# pir.net
KiCad netlist of a schematic drawn in Altium Designer
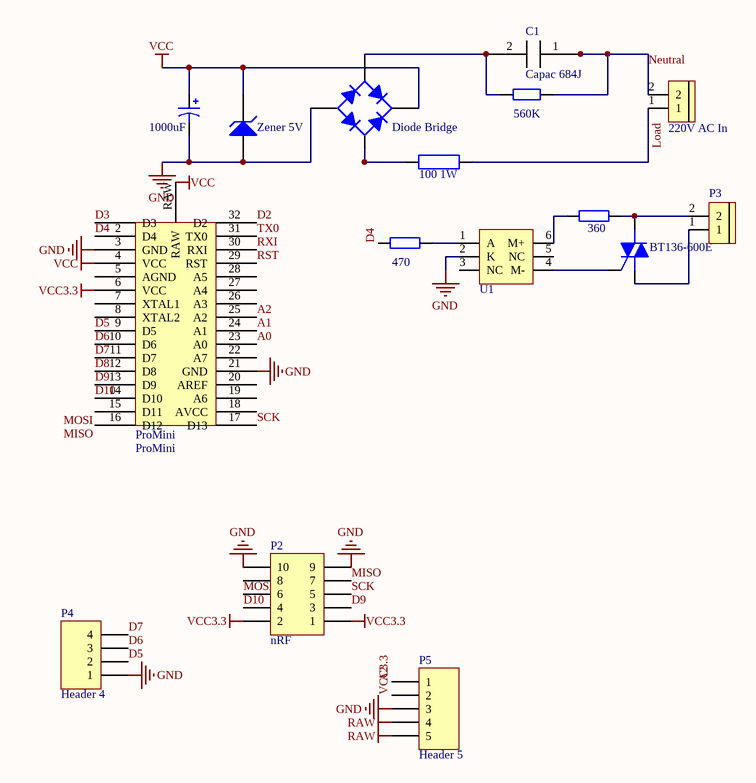
[diagram p0: pir.SchDoc]

(export (version "E")
  (design (tool "Eeschema 10.0.6"))
  (components
    (comp (ref "C1")
      (value "Capac 684J")
      (footprint "Tu keo 684J 400V")
      (libsource (lib "ArduinoLib") (part "Tu keo 684J 400V"))
    )
    (comp (ref "C3")
      (value "1000uF")
      (footprint "C10mm")
      (description "Polarized Capacitor (Axial)")
      (fields (field (name "PUBLISHER") "Altium Limited"))
      (libsource (lib "NBBLib 14-03-2012") (part "Cap Pol 8mm"))
    )
    (comp (ref "D1")
      (value "Diode Bridge")
      (footprint "D-38")
      (description "Full Wave Diode Bridge")
      (fields (field (name "PUBLISHER") "Altium Limited"))
      (libsource (lib "Miscellaneous Devices") (part "Bridge1"))
    )
    (comp (ref "D3")
      (value "Zener 5V")
      (footprint "DIODE/NOM/0.5A")
      (description "Zener Diode")
      (fields (field (name "VOLTAGE") "5") (field (name "PUBLISHER") "Altium Limited"))
      (libsource (lib "NBBLib 14-03-2012") (part "Diode Zener"))
    )
    (comp (ref "P1")
      (value "220V AC In")
      (footprint "BIG_Header 2")
      (libsource (lib "NBBLib 14-03-2012") (part "BIG_Header 2"))
    )
    (comp (ref "P2")
      (value "nRF")
      (footprint "HDR2X5")
      (description "Header, 5-Pin, Dual row")
      (fields (field (name "PUBLISHER") "Altium Limited"))
      (libsource (lib "Miscellaneous Connectors") (part "Header 5X2"))
    )
    (comp (ref "P3")
      (value "BIG_Header 2")
      (footprint "BIG_Header 2")
      (libsource (lib "NBBLib 14-03-2012") (part "BIG_Header 2"))
    )
    (comp (ref "P4")
      (value "Header 4")
      (footprint "HDR1X4")
      (description "Header, 4-Pin")
      (fields (field (name "PUBLISHER") "Altium Limited"))
      (libsource (lib "Miscellaneous Connectors") (part "Header 4"))
    )
    (comp (ref "P5")
      (value "Header 5")
      (footprint "HDR1X5")
      (description "Header, 5-Pin")
      (fields (field (name "PUBLISHER") "Altium Limited"))
      (libsource (lib "NBBLib 14-03-2012") (part "Header 5"))
    )
    (comp (ref "ProMini")
      (value "ProMini")
      (footprint "Arduino Pro Mini")
      (libsource (lib "ArduinoLib") (part "Pro Mini"))
    )
    (comp (ref "Q1")
      (value "BT136-600E")
      (footprint "BTA6-600")
      (description "Silicon Bidirectional Triode Thyristor")
      (fields (field (name "PUBLISHER") "Altium Limited"))
      (libsource (lib "NBBLib 14-03-2012") (part "BTA12-600"))
    )
    (comp (ref "R1")
      (value "100 1W")
      (footprint "DIEN TRO 1W (tube)")
      (description "1W Res Power")
      (fields (field (name "VOLTAGE") "400") (field (name "CREATOR") "Nguyen Ba Bien"))
      (libsource (lib "NBBLib 14-03-2012") (part "Res 1W"))
    )
    (comp (ref "R3")
      (value "560K")
      (footprint "AXIAL-0.4")
      (description "Resistor")
      (fields (field (name "PUBLISHER") "Altium Limited"))
      (libsource (lib "Miscellaneous Devices") (part "Res2"))
    )
    (comp (ref "R4")
      (value "470")
      (footprint "R1/4W")
      (description "Resistor")
      (libsource (lib "t.thien") (part "R1/4W"))
    )
    (comp (ref "R5")
      (value "360")
      (footprint "R1/4W")
      (description "Resistor")
      (libsource (lib "t.thien") (part "R1/4W"))
    )
    (comp (ref "U1")
      (value "MOC3021M")
      (footprint "MOC30XX")
      (libsource (lib "NBBLib 14-03-2012") (part "MOC3021M"))
    )
  )
  (nets
    (net (code "1") (name "/A0") (class "Default")
      (node (ref "ProMini") (pin "23") (pinfunction "A0_23") (pintype "passive"))
    )
    (net (code "2") (name "/A1") (class "Default")
      (node (ref "ProMini") (pin "24") (pinfunction "A1_24") (pintype "passive"))
    )
    (net (code "3") (name "/A2") (class "Default")
      (node (ref "P5") (pin "1") (pinfunction "1_1") (pintype "passive"))
      (node (ref "ProMini") (pin "25") (pinfunction "A2_25") (pintype "passive"))
    )
    (net (code "4") (name "/D2") (class "Default")
      (node (ref "ProMini") (pin "32") (pinfunction "D2_32") (pintype "passive"))
    )
    (net (code "5") (name "/D3") (class "Default")
      (node (ref "ProMini") (pin "1") (pinfunction "D3_1") (pintype "passive"))
    )
    (net (code "6") (name "/D4") (class "Default")
      (node (ref "ProMini") (pin "2") (pinfunction "D4_2") (pintype "passive"))
      (node (ref "R4") (pin "1") (pinfunction "1_1") (pintype "passive"))
    )
    (net (code "7") (name "/D5") (class "Default")
      (node (ref "P4") (pin "2") (pinfunction "2_2") (pintype "passive"))
      (node (ref "ProMini") (pin "9") (pinfunction "D5_9") (pintype "passive"))
    )
    (net (code "8") (name "/D6") (class "Default")
      (node (ref "P4") (pin "3") (pinfunction "3_3") (pintype "passive"))
      (node (ref "ProMini") (pin "10") (pinfunction "D6_10") (pintype "passive"))
    )
    (net (code "9") (name "/D7") (class "Default")
      (node (ref "P4") (pin "4") (pinfunction "4_4") (pintype "passive"))
      (node (ref "ProMini") (pin "11") (pinfunction "D7_11") (pintype "passive"))
    )
    (net (code "10") (name "/D8") (class "Default")
      (node (ref "ProMini") (pin "12") (pinfunction "D8_12") (pintype "passive"))
    )
    (net (code "11") (name "/D9") (class "Default")
      (node (ref "P2") (pin "3") (pinfunction "3_3") (pintype "passive"))
      (node (ref "ProMini") (pin "13") (pinfunction "D9_13") (pintype "passive"))
    )
    (net (code "12") (name "/D10") (class "Default")
      (node (ref "P2") (pin "4") (pinfunction "4_4") (pintype "passive"))
      (node (ref "ProMini") (pin "14") (pinfunction "D10_14") (pintype "passive"))
    )
    (net (code "13") (name "/Load") (class "Default")
      (node (ref "P1") (pin "1") (pinfunction "1_1") (pintype "passive"))
      (node (ref "R1") (pin "2") (pinfunction "2_2") (pintype "passive"))
    )
    (net (code "14") (name "/MISO") (class "Default")
      (node (ref "P2") (pin "7") (pinfunction "7_7") (pintype "passive"))
      (node (ref "ProMini") (pin "16") (pinfunction "D12_16") (pintype "passive"))
    )
    (net (code "15") (name "/MOSI") (class "Default")
      (node (ref "P2") (pin "6") (pinfunction "6_6") (pintype "passive"))
      (node (ref "ProMini") (pin "15") (pinfunction "D11_15") (pintype "passive"))
    )
    (net (code "16") (name "/Neutral") (class "Default")
      (node (ref "C1") (pin "1") (pinfunction "1_1") (pintype "passive"))
      (node (ref "P1") (pin "2") (pinfunction "2_2") (pintype "passive"))
      (node (ref "R3") (pin "2") (pinfunction "2_2") (pintype "passive"))
    )
    (net (code "17") (name "/RST") (class "Default")
      (node (ref "ProMini") (pin "29") (pinfunction "RST_29") (pintype "passive"))
    )
    (net (code "18") (name "/RXI") (class "Default")
      (node (ref "ProMini") (pin "30") (pinfunction "RXI_30") (pintype "passive"))
    )
    (net (code "19") (name "/SCK") (class "Default")
      (node (ref "P2") (pin "5") (pinfunction "5_5") (pintype "passive"))
      (node (ref "ProMini") (pin "17") (pinfunction "D13_17") (pintype "passive"))
    )
    (net (code "20") (name "/TX0") (class "Default")
      (node (ref "ProMini") (pin "31") (pinfunction "TX0_31") (pintype "passive"))
    )
    (net (code "21") (name "GND") (class "Default")
      (node (ref "C3") (pin "2") (pinfunction "2_2") (pintype "passive"))
      (node (ref "D1") (pin "3") (pinfunction "A_3") (pintype "passive"))
      (node (ref "D3") (pin "1") (pinfunction "A_1") (pintype "passive"))
      (node (ref "P2") (pin "10") (pinfunction "10_10") (pintype "passive"))
      (node (ref "P2") (pin "9") (pinfunction "9_9") (pintype "passive"))
      (node (ref "P4") (pin "1") (pinfunction "1_1") (pintype "passive"))
      (node (ref "P5") (pin "3") (pinfunction "3_3") (pintype "passive"))
      (node (ref "ProMini") (pin "21") (pinfunction "GND_21") (pintype "passive"))
      (node (ref "ProMini") (pin "3") (pinfunction "GND_3") (pintype "passive"))
      (node (ref "U1") (pin "2") (pinfunction "K_2") (pintype "passive"))
    )
    (net (code "22") (name "Net-(C1-Pad2)") (class "Default")
      (node (ref "C1") (pin "2") (pinfunction "2_2") (pintype "passive"))
      (node (ref "D1") (pin "4") (pinfunction "C_4") (pintype "passive"))
      (node (ref "R3") (pin "1") (pinfunction "1_1") (pintype "passive"))
    )
    (net (code "23") (name "Net-(D1-C-Pad2)") (class "Default")
      (node (ref "D1") (pin "2") (pinfunction "C_2") (pintype "passive"))
      (node (ref "R1") (pin "1") (pinfunction "1_1") (pintype "passive"))
    )
    (net (code "24") (name "Net-(Q1-G)") (class "Default")
      (node (ref "Q1") (pin "3") (pinfunction "G_3") (pintype "passive"))
      (node (ref "U1") (pin "4") (pinfunction "M-_4") (pintype "passive"))
    )
    (net (code "25") (name "Net-(Q1-M1)") (class "Default")
      (node (ref "P3") (pin "1") (pinfunction "1_1") (pintype "passive"))
      (node (ref "Q1") (pin "1") (pinfunction "M1_1") (pintype "passive"))
    )
    (net (code "26") (name "Net-(Q1-M2)") (class "Default")
      (node (ref "P3") (pin "2") (pinfunction "2_2") (pintype "passive"))
      (node (ref "Q1") (pin "2") (pinfunction "M2_2") (pintype "passive"))
      (node (ref "R5") (pin "2") (pinfunction "2_2") (pintype "passive"))
    )
    (net (code "27") (name "Net-(U1-A)") (class "Default")
      (node (ref "R4") (pin "2") (pinfunction "2_2") (pintype "passive"))
      (node (ref "U1") (pin "1") (pinfunction "A_1") (pintype "passive"))
    )
    (net (code "28") (name "Net-(U1-M+)") (class "Default")
      (node (ref "R5") (pin "1") (pinfunction "1_1") (pintype "passive"))
      (node (ref "U1") (pin "6") (pinfunction "M+_6") (pintype "passive"))
    )
    (net (code "29") (name "RAW") (class "Default")
      (node (ref "P5") (pin "4") (pinfunction "4_4") (pintype "passive"))
      (node (ref "P5") (pin "5") (pinfunction "5_5") (pintype "passive"))
    )
    (net (code "30") (name "VCC") (class "Default")
      (node (ref "C3") (pin "1") (pinfunction "1_1") (pintype "passive"))
      (node (ref "D1") (pin "1") (pinfunction "K_1") (pintype "passive"))
      (node (ref "D3") (pin "2") (pinfunction "K_2") (pintype "passive"))
      (node (ref "ProMini") (pin "4") (pinfunction "VCC_4") (pintype "passive"))
      (node (ref "ProMini") (pin "RAW") (pinfunction "RAW_RAW") (pintype "passive"))
    )
    (net (code "31") (name "VCC3.3") (class "Default")
      (node (ref "P2") (pin "1") (pinfunction "1_1") (pintype "passive"))
      (node (ref "P2") (pin "2") (pinfunction "2_2") (pintype "passive"))
      (node (ref "P5") (pin "2") (pinfunction "2_2") (pintype "passive"))
      (node (ref "ProMini") (pin "6") (pinfunction "VCC_6") (pintype "passive"))
    )
    (net (code "32") (name "unconnected-(P2-Pad8)") (class "Default")
      (node (ref "P2") (pin "8") (pinfunction "8_8") (pintype "passive"))
    )
    (net (code "33") (name "unconnected-(ProMini-A3-Pad26)") (class "Default")
      (node (ref "ProMini") (pin "26") (pinfunction "A3_26") (pintype "passive"))
    )
    (net (code "34") (name "unconnected-(ProMini-A4-Pad27)") (class "Default")
      (node (ref "ProMini") (pin "27") (pinfunction "A4_27") (pintype "passive"))
    )
    (net (code "35") (name "unconnected-(ProMini-A5-Pad28)") (class "Default")
      (node (ref "ProMini") (pin "28") (pinfunction "A5_28") (pintype "passive"))
    )
    (net (code "36") (name "unconnected-(ProMini-A6-Pad19)") (class "Default")
      (node (ref "ProMini") (pin "19") (pinfunction "A6_19") (pintype "passive"))
    )
    (net (code "37") (name "unconnected-(ProMini-A7-Pad22)") (class "Default")
      (node (ref "ProMini") (pin "22") (pinfunction "A7_22") (pintype "passive"))
    )
    (net (code "38") (name "unconnected-(ProMini-AGND-Pad5)") (class "Default")
      (node (ref "ProMini") (pin "5") (pinfunction "AGND_5") (pintype "passive"))
    )
    (net (code "39") (name "unconnected-(ProMini-AREF-Pad20)") (class "Default")
      (node (ref "ProMini") (pin "20") (pinfunction "AREF_20") (pintype "passive"))
    )
    (net (code "40") (name "unconnected-(ProMini-AVCC-Pad18)") (class "Default")
      (node (ref "ProMini") (pin "18") (pinfunction "AVCC_18") (pintype "passive"))
    )
    (net (code "41") (name "unconnected-(ProMini-XTAL1-Pad7)") (class "Default")
      (node (ref "ProMini") (pin "7") (pinfunction "XTAL1_7") (pintype "passive"))
    )
    (net (code "42") (name "unconnected-(ProMini-XTAL2-Pad8)") (class "Default")
      (node (ref "ProMini") (pin "8") (pinfunction "XTAL2_8") (pintype "passive"))
    )
    (net (code "43") (name "unconnected-(U1-NC-Pad3)") (class "Default")
      (node (ref "U1") (pin "3") (pinfunction "NC_3") (pintype "passive"))
    )
    (net (code "44") (name "unconnected-(U1-NC-Pad5)") (class "Default")
      (node (ref "U1") (pin "5") (pinfunction "NC_5") (pintype "passive"))
    )
  )
)
